# HVSUP_channel.net
KiCad netlist of a schematic drawn in Altium Designer
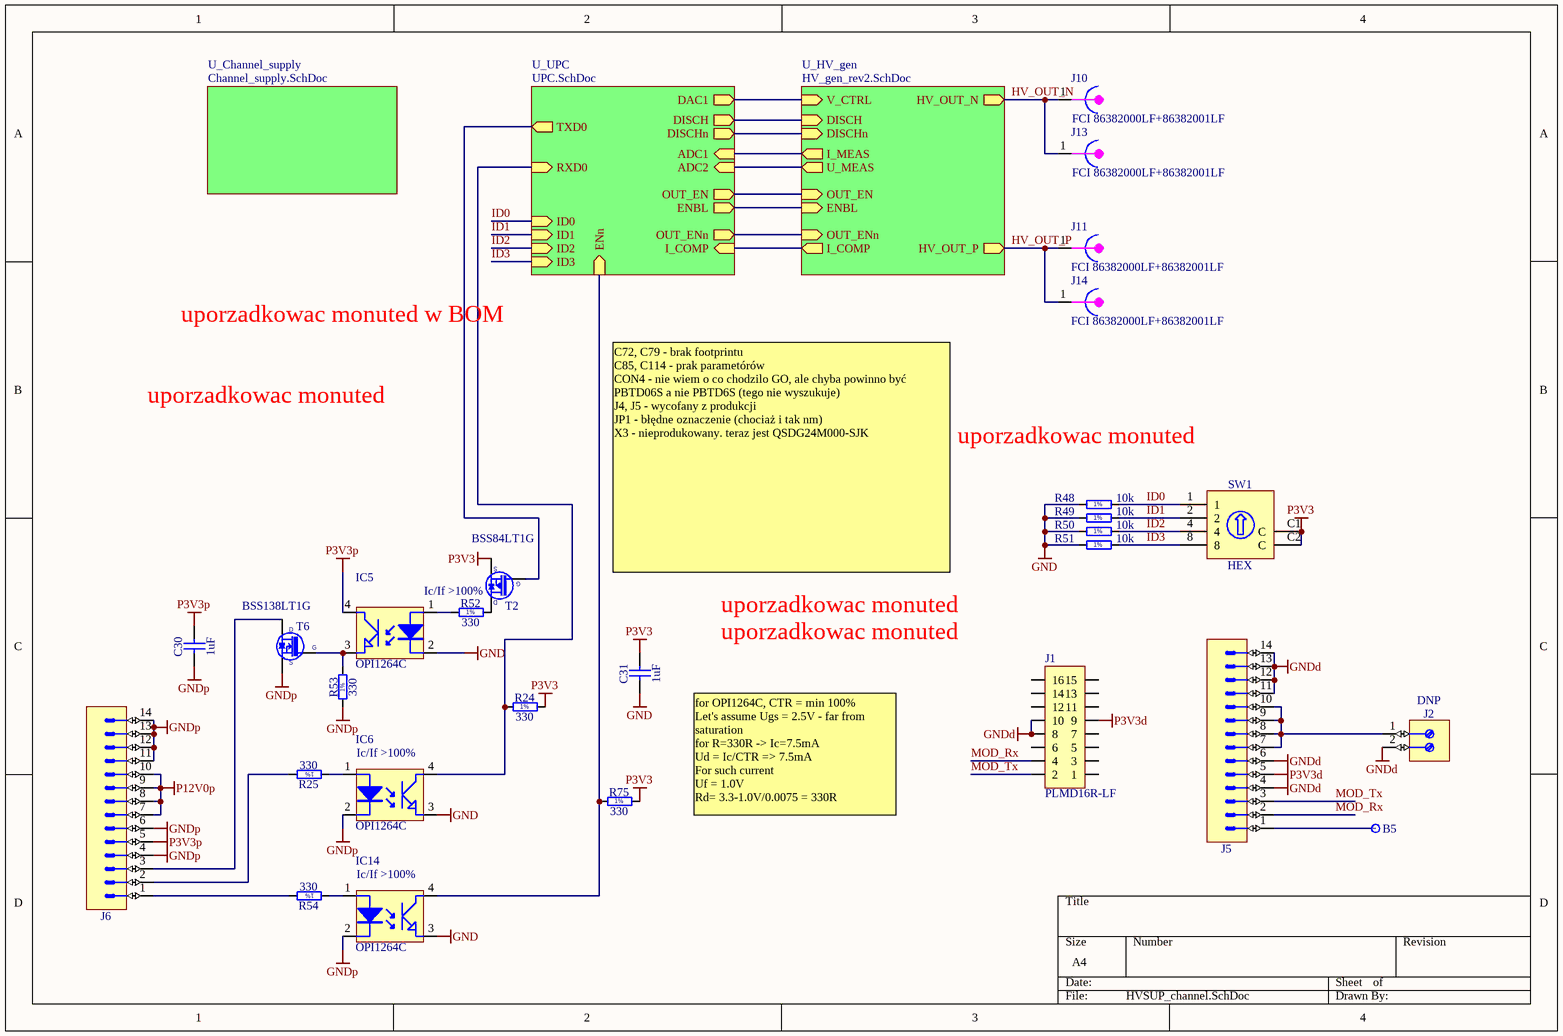
[diagram p0: HVSUP_channel.SchDoc]

(export (version "E")
  (design (tool "Eeschema 10.0.6"))
  (components
    (comp (ref "B5")
      (value "Plated Hole")
      (footprint "c130h80")
      (description "Single Terminal Socket")
      (fields (field (name "PART NUMBER") "PLATED_HOLE0.8_PAD1.3") (field (name "AUTHOR") "CERN DEM JLC"))
      (libsource (lib "Eletro-mechanical") (part "Single Terminal Socket"))
    )
    (comp (ref "C30")
      (value "1uF")
      (footprint "CAPC1005X55N")
      (description "Non-polarised capacitor")
      (fields
        (field (name "PART NUMBER") "CC0402_1UF_16V_10%_X5R")
        (field (name "VOLTAGE") "16V")
        (field (name "AUTHOR") "CERN DEM JLC")
      )
      (libsource (lib "Capacitors") (part "Capacitor - non polarized"))
    )
    (comp (ref "C31")
      (value "1uF")
      (footprint "CAPC1005X55N")
      (description "Non-polarised capacitor")
      (fields
        (field (name "PART NUMBER") "CC0402_1UF_16V_10%_X5R")
        (field (name "VOLTAGE") "16V")
        (field (name "AUTHOR") "CERN DEM JLC")
      )
      (libsource (lib "Capacitors") (part "Capacitor - non polarized"))
    )
    (comp (ref "IC5")
      (value "OPI1264C")
      (footprint "OPI1264C")
      (description "10kV opto-coupler")
      (libsource (lib "LIBRARY_SCH") (part "OPTO-OPI1264C"))
    )
    (comp (ref "IC6")
      (value "OPI1264C")
      (footprint "OPI1264C")
      (description "10kV opto-coupler")
      (libsource (lib "") (part "OPTO-OPI1264C_1"))
    )
    (comp (ref "IC14")
      (value "OPI1264C")
      (footprint "OPI1264C")
      (description "10kV opto-coupler")
      (libsource (lib "") (part "OPTO-OPI1264C_1"))
    )
    (comp (ref "J1")
      (value "PLMD16R-LF")
      (footprint "PLMD16R-LF")
      (description "2mm  dual row goldpin (Maritex)")
      (libsource (lib "LIBRARY_SCH") (part "CON_2x8 2mm_RA_male"))
    )
    (comp (ref "J2")
      (value "DNP")
      (footprint "PHOENIX_1725656")
      (description "Terminal Block, 2 Positions, Screw Connection")
      (fields
        (field (name "PART NUMBER") "PHOENIX_1725656")
        (field (name "MANUFACTURER") "PHOENIX CONTACT")
        (field (name "AUTHOR") "CERN DEM JMW")
      )
      (libsource (lib "Connectors") (part "Terminal Block_2 Positions_Screw Connection"))
    )
    (comp (ref "J5")
      (value "Header 14")
      (footprint "3M_N2514-5002RB")
      (description "Connector 14 Male")
      (fields
        (field (name "PART NUMBER") "3M_N2514-5002RB")
        (field (name "MANUFACTURER") "3M")
        (field (name "AUTHOR") "CERN DEM JLC")
      )
      (libsource (lib "Connectors") (part "Connector 14 Male"))
    )
    (comp (ref "J6")
      (value "Header 14")
      (footprint "3M_N2514-5002RB")
      (description "Connector 14 Male")
      (fields
        (field (name "PART NUMBER") "3M_N2514-5002RB")
        (field (name "MANUFACTURER") "3M")
        (field (name "AUTHOR") "CERN DEM JLC")
      )
      (libsource (lib "Connectors") (part "Connector 14 Male"))
    )
    (comp (ref "J10")
      (value "FCI 86382000LF+86382001LF")
      (footprint "FCI_86382000LF")
      (description "D-SUB HIGH VOLTAGE CONTACT PIN")
      (libsource (lib "LIBRARY_SCH") (part "CON_HV_DSUB_PIN"))
    )
    (comp (ref "J11")
      (value "FCI 86382000LF+86382001LF")
      (footprint "FCI_86382000LF")
      (description "D-SUB HIGH VOLTAGE CONTACT PIN")
      (libsource (lib "LIBRARY_SCH") (part "CON_HV_DSUB_PIN"))
    )
    (comp (ref "J13")
      (value "FCI 86382000LF+86382001LF")
      (footprint "FCI_86382000LF")
      (description "D-SUB HIGH VOLTAGE CONTACT PIN")
      (libsource (lib "LIBRARY_SCH") (part "CON_HV_DSUB_PIN"))
    )
    (comp (ref "J14")
      (value "FCI 86382000LF+86382001LF")
      (footprint "FCI_86382000LF")
      (description "D-SUB HIGH VOLTAGE CONTACT PIN")
      (libsource (lib "LIBRARY_SCH") (part "CON_HV_DSUB_PIN"))
    )
    (comp (ref "R24")
      (value "330")
      (footprint "RESC1005X40N")
      (description "Resistor - 1%")
      (fields
        (field (name "PART NUMBER") "R0402_330R_1%_0.0625W_100PPM")
        (field (name "POWER") "0.0625W")
        (field (name "AUTHOR") "CERN DEM JLC")
      )
      (libsource (lib "Resistors") (part "Resistor - 1%"))
    )
    (comp (ref "R25")
      (value "330")
      (footprint "RESC1005X40N")
      (description "Resistor - 1%")
      (fields
        (field (name "PART NUMBER") "R0402_330R_1%_0.0625W_100PPM")
        (field (name "POWER") "0.0625W")
        (field (name "AUTHOR") "CERN DEM JLC")
      )
      (libsource (lib "Resistors") (part "Resistor - 1%"))
    )
    (comp (ref "R48")
      (value "10k")
      (footprint "RESC1005X40N")
      (description "Resistor - 1%")
      (fields
        (field (name "PART NUMBER") "R0402_10K_1%_0.0625W_100PPM")
        (field (name "POWER") "0.0625W")
        (field (name "AUTHOR") "CERN DEM JLC")
      )
      (libsource (lib "Resistors") (part "Resistor - 1%"))
    )
    (comp (ref "R49")
      (value "10k")
      (footprint "RESC1005X40N")
      (description "Resistor - 1%")
      (fields
        (field (name "PART NUMBER") "R0402_10K_1%_0.0625W_100PPM")
        (field (name "POWER") "0.0625W")
        (field (name "AUTHOR") "CERN DEM JLC")
      )
      (libsource (lib "Resistors") (part "Resistor - 1%"))
    )
    (comp (ref "R50")
      (value "10k")
      (footprint "RESC1005X40N")
      (description "Resistor - 1%")
      (fields
        (field (name "PART NUMBER") "R0402_10K_1%_0.0625W_100PPM")
        (field (name "POWER") "0.0625W")
        (field (name "AUTHOR") "CERN DEM JLC")
      )
      (libsource (lib "Resistors") (part "Resistor - 1%"))
    )
    (comp (ref "R51")
      (value "10k")
      (footprint "RESC1005X40N")
      (description "Resistor - 1%")
      (fields
        (field (name "PART NUMBER") "R0402_10K_1%_0.0625W_100PPM")
        (field (name "POWER") "0.0625W")
        (field (name "AUTHOR") "CERN DEM JLC")
      )
      (libsource (lib "Resistors") (part "Resistor - 1%"))
    )
    (comp (ref "R52")
      (value "330")
      (footprint "RESC1005X40N")
      (description "Resistor - 1%")
      (fields
        (field (name "PART NUMBER") "R0402_330R_1%_0.0625W_100PPM")
        (field (name "POWER") "0.0625W")
        (field (name "AUTHOR") "CERN DEM JLC")
      )
      (libsource (lib "Resistors") (part "Resistor - 1%"))
    )
    (comp (ref "R53")
      (value "330")
      (footprint "RESC1005X40N")
      (description "Resistor - 1%")
      (fields
        (field (name "PART NUMBER") "R0402_330R_1%_0.0625W_100PPM")
        (field (name "POWER") "0.0625W")
        (field (name "AUTHOR") "CERN DEM JLC")
      )
      (libsource (lib "Resistors") (part "Resistor - 1%"))
    )
    (comp (ref "R54")
      (value "330")
      (footprint "RESC1005X40N")
      (description "Resistor - 1%")
      (fields
        (field (name "PART NUMBER") "R0402_330R_1%_0.0625W_100PPM")
        (field (name "POWER") "0.0625W")
        (field (name "AUTHOR") "CERN DEM JLC")
      )
      (libsource (lib "Resistors") (part "Resistor - 1%"))
    )
    (comp (ref "R75")
      (value "330")
      (footprint "RESC1005X40N")
      (description "Resistor - 1%")
      (fields
        (field (name "PART NUMBER") "R0402_330R_1%_0.0625W_100PPM")
        (field (name "POWER") "0.0625W")
        (field (name "AUTHOR") "CERN DEM JLC")
      )
      (libsource (lib "Resistors") (part "Resistor - 1%"))
    )
    (comp (ref "SW1")
      (value "HEX")
      (footprint "SW_OMRON_A6RV-162RF")
      (description "Rotary Code Switch 1 2 4 8 C1 C2")
      (fields
        (field (name "PART NUMBER") "SW_OMRON_A6RV-162RF or ERD716RR")
        (field (name "MANUFACTURER") "OMRON")
        (field (name "AUTHOR") "CERN DEM JLC")
      )
      (libsource (lib "Eletro-mechanical") (part "SW Rotary 1 2 4 8 C1 C2"))
    )
    (comp (ref "T2")
      (value "BSS84LT1G")
      (footprint "SOT95P240X110-3N")
      (description "P-CHANNEL MOSFET WITH DIODE")
      (fields (field (name "MANUFACTURER") "ON SEMICONDUCTOR") (field (name "AUTHOR") "CERN DEM JLC"))
      (libsource (lib "ICs And Semiconductors") (part "P-MOSFET-D 1G 2S 3D"))
    )
    (comp (ref "T6")
      (value "BSS138LT1G")
      (footprint "SOT95P240X110-3N")
      (description "N-CHANNEL MOSFET WITH DIODE")
      (fields (field (name "MANUFACTURER") "ON SEMICONDUCTOR") (field (name "AUTHOR") "CERN DEM JLC"))
      (libsource (lib "ICs And Semiconductors") (part "N-MOSFET-D 1G 2S 3D"))
    )
  )
  (nets
    (net (code "5") (name "/ENn") (class "Default")
      (node (ref "IC14") (pin "4") (pinfunction "C_4") (pintype "passive"))
      (node (ref "R75") (pin "1") (pinfunction "1_1") (pintype "passive"))
    )
    (net (code "6") (name "/HV_OUT_N") (class "Default")
      (node (ref "J10") (pin "1") (pintype "passive"))
      (node (ref "J13") (pin "1") (pintype "passive"))
    )
    (net (code "7") (name "/HV_OUT_P") (class "Default")
      (node (ref "J11") (pin "1") (pintype "passive"))
      (node (ref "J14") (pin "1") (pintype "passive"))
    )
    (net (code "8") (name "/ID0") (class "Default")
      (node (ref "R48") (pin "2") (pinfunction "2_2") (pintype "passive"))
      (node (ref "SW1") (pin "1") (pinfunction "1_1") (pintype "passive"))
    )
    (net (code "9") (name "/ID1") (class "Default")
      (node (ref "R49") (pin "2") (pinfunction "2_2") (pintype "passive"))
      (node (ref "SW1") (pin "2") (pinfunction "2_2") (pintype "passive"))
    )
    (net (code "10") (name "/ID2") (class "Default")
      (node (ref "R50") (pin "2") (pinfunction "2_2") (pintype "passive"))
      (node (ref "SW1") (pin "4") (pinfunction "4_4") (pintype "passive"))
    )
    (net (code "11") (name "/ID3") (class "Default")
      (node (ref "R51") (pin "2") (pinfunction "2_2") (pintype "passive"))
      (node (ref "SW1") (pin "8") (pinfunction "8_8") (pintype "passive"))
    )
    (net (code "14") (name "/MOD_Rx") (class "Default")
      (node (ref "J1") (pin "4") (pinfunction "4_4") (pintype "passive"))
      (node (ref "J5") (pin "2") (pinfunction "2_2") (pintype "bidirectional"))
    )
    (net (code "15") (name "/MOD_Tx") (class "Default")
      (node (ref "J1") (pin "2") (pinfunction "2_2") (pintype "passive"))
      (node (ref "J5") (pin "3") (pinfunction "3_3") (pintype "bidirectional"))
    )
    (net (code "18") (name "/RXD0") (class "Default")
      (node (ref "IC6") (pin "4") (pinfunction "C_4") (pintype "passive"))
      (node (ref "R24") (pin "1") (pinfunction "1_1") (pintype "passive"))
    )
    (net (code "19") (name "/TXD0") (class "Default")
      (node (ref "T2") (pin "1") (pinfunction "G_1") (pintype "passive"))
    )
    (net (code "21") (name "GND") (class "Default")
      (node (ref "C31") (pin "1") (pinfunction "1_1") (pintype "passive"))
      (node (ref "IC14") (pin "3") (pinfunction "E_3") (pintype "passive"))
      (node (ref "IC5") (pin "2") (pinfunction "K_2") (pintype "passive"))
      (node (ref "IC6") (pin "3") (pinfunction "E_3") (pintype "passive"))
      (node (ref "R48") (pin "1") (pinfunction "1_1") (pintype "passive"))
      (node (ref "R49") (pin "1") (pinfunction "1_1") (pintype "passive"))
      (node (ref "R50") (pin "1") (pinfunction "1_1") (pintype "passive"))
      (node (ref "R51") (pin "1") (pinfunction "1_1") (pintype "passive"))
    )
    (net (code "22") (name "GNDd") (class "Default")
      (node (ref "J1") (pin "10") (pinfunction "10_10") (pintype "passive"))
      (node (ref "J1") (pin "8") (pinfunction "8_8") (pintype "passive"))
      (node (ref "J2") (pin "2") (pinfunction "2_2") (pintype "bidirectional"))
      (node (ref "J5") (pin "11") (pinfunction "11_11") (pintype "bidirectional"))
      (node (ref "J5") (pin "12") (pinfunction "12_12") (pintype "bidirectional"))
      (node (ref "J5") (pin "13") (pinfunction "13_13") (pintype "bidirectional"))
      (node (ref "J5") (pin "14") (pinfunction "14_14") (pintype "bidirectional"))
      (node (ref "J5") (pin "4") (pinfunction "4_4") (pintype "bidirectional"))
      (node (ref "J5") (pin "6") (pinfunction "6_6") (pintype "bidirectional"))
    )
    (net (code "23") (name "GNDp") (class "Default")
      (node (ref "C30") (pin "1") (pinfunction "1_1") (pintype "passive"))
      (node (ref "IC14") (pin "2") (pinfunction "K_2") (pintype "passive"))
      (node (ref "IC6") (pin "2") (pinfunction "K_2") (pintype "passive"))
      (node (ref "J6") (pin "11") (pinfunction "11_11") (pintype "bidirectional"))
      (node (ref "J6") (pin "12") (pinfunction "12_12") (pintype "bidirectional"))
      (node (ref "J6") (pin "13") (pinfunction "13_13") (pintype "bidirectional"))
      (node (ref "J6") (pin "14") (pinfunction "14_14") (pintype "bidirectional"))
      (node (ref "J6") (pin "4") (pinfunction "4_4") (pintype "bidirectional"))
      (node (ref "J6") (pin "6") (pinfunction "6_6") (pintype "bidirectional"))
      (node (ref "R53") (pin "1") (pinfunction "1_1") (pintype "passive"))
      (node (ref "T6") (pin "2") (pinfunction "S_2") (pintype "passive"))
    )
    (net (code "24") (name "Net-(B5-Pad1)") (class "Default")
      (node (ref "B5") (pin "1") (pinfunction "1_1") (pintype "bidirectional"))
      (node (ref "J5") (pin "1") (pinfunction "1_1") (pintype "bidirectional"))
    )
    (net (code "25") (name "Net-(IC5-A)") (class "Default")
      (node (ref "IC5") (pin "1") (pinfunction "A_1") (pintype "passive"))
      (node (ref "R52") (pin "1") (pinfunction "1_1") (pintype "passive"))
    )
    (net (code "26") (name "Net-(IC5-E)") (class "Default")
      (node (ref "IC5") (pin "3") (pinfunction "E_3") (pintype "passive"))
      (node (ref "R53") (pin "2") (pinfunction "2_2") (pintype "passive"))
      (node (ref "T6") (pin "1") (pinfunction "G_1") (pintype "passive"))
    )
    (net (code "27") (name "Net-(IC6-A)") (class "Default")
      (node (ref "IC6") (pin "1") (pinfunction "A_1") (pintype "passive"))
      (node (ref "R25") (pin "1") (pinfunction "1_1") (pintype "passive"))
    )
    (net (code "28") (name "Net-(IC14-A)") (class "Default")
      (node (ref "IC14") (pin "1") (pinfunction "A_1") (pintype "passive"))
      (node (ref "R54") (pin "1") (pinfunction "1_1") (pintype "passive"))
    )
    (net (code "29") (name "Net-(J2-Pad1)") (class "Default")
      (node (ref "J2") (pin "1") (pinfunction "1_1") (pintype "bidirectional"))
      (node (ref "J5") (pin "10") (pinfunction "10_10") (pintype "bidirectional"))
      (node (ref "J5") (pin "7") (pinfunction "7_7") (pintype "bidirectional"))
      (node (ref "J5") (pin "8") (pinfunction "8_8") (pintype "bidirectional"))
      (node (ref "J5") (pin "9") (pinfunction "9_9") (pintype "bidirectional"))
    )
    (net (code "30") (name "Net-(J6-Pad1)") (class "Default")
      (node (ref "J6") (pin "1") (pinfunction "1_1") (pintype "bidirectional"))
      (node (ref "R54") (pin "2") (pinfunction "2_2") (pintype "passive"))
    )
    (net (code "31") (name "Net-(J6-Pad2)") (class "Default")
      (node (ref "J6") (pin "2") (pinfunction "2_2") (pintype "bidirectional"))
      (node (ref "R25") (pin "2") (pinfunction "2_2") (pintype "passive"))
    )
    (net (code "32") (name "Net-(T2-D)") (class "Default")
      (node (ref "R52") (pin "2") (pinfunction "2_2") (pintype "passive"))
      (node (ref "T2") (pin "3") (pinfunction "D_3") (pintype "passive"))
    )
    (net (code "33") (name "Net-(T6-D)") (class "Default")
      (node (ref "J6") (pin "3") (pinfunction "3_3") (pintype "bidirectional"))
      (node (ref "T6") (pin "3") (pinfunction "D_3") (pintype "passive"))
    )
    (net (code "34") (name "P3V3") (class "Default")
      (node (ref "C31") (pin "2") (pinfunction "2_2") (pintype "passive"))
      (node (ref "R24") (pin "2") (pinfunction "2_2") (pintype "passive"))
      (node (ref "R75") (pin "2") (pinfunction "2_2") (pintype "passive"))
      (node (ref "SW1") (pin "C1") (pinfunction "C_C1") (pintype "passive"))
      (node (ref "SW1") (pin "C2") (pinfunction "C_C2") (pintype "passive"))
      (node (ref "T2") (pin "2") (pinfunction "S_2") (pintype "passive"))
    )
    (net (code "35") (name "P3V3d") (class "Default")
      (node (ref "J1") (pin "9") (pinfunction "9_9") (pintype "passive"))
      (node (ref "J5") (pin "5") (pinfunction "5_5") (pintype "bidirectional"))
    )
    (net (code "36") (name "P3V3p") (class "Default")
      (node (ref "C30") (pin "2") (pinfunction "2_2") (pintype "passive"))
      (node (ref "IC5") (pin "4") (pinfunction "C_4") (pintype "passive"))
      (node (ref "J6") (pin "5") (pinfunction "5_5") (pintype "bidirectional"))
    )
    (net (code "37") (name "P12V0p") (class "Default")
      (node (ref "J6") (pin "10") (pinfunction "10_10") (pintype "bidirectional"))
      (node (ref "J6") (pin "7") (pinfunction "7_7") (pintype "bidirectional"))
      (node (ref "J6") (pin "8") (pinfunction "8_8") (pintype "bidirectional"))
      (node (ref "J6") (pin "9") (pinfunction "9_9") (pintype "bidirectional"))
    )
    (net (code "38") (name "unconnected-(J1-Pad1)") (class "Default")
      (node (ref "J1") (pin "1") (pinfunction "1_1") (pintype "passive"))
    )
    (net (code "39") (name "unconnected-(J1-Pad3)") (class "Default")
      (node (ref "J1") (pin "3") (pinfunction "3_3") (pintype "passive"))
    )
    (net (code "40") (name "unconnected-(J1-Pad5)") (class "Default")
      (node (ref "J1") (pin "5") (pinfunction "5_5") (pintype "passive"))
    )
    (net (code "41") (name "unconnected-(J1-Pad6)") (class "Default")
      (node (ref "J1") (pin "6") (pinfunction "6_6") (pintype "passive"))
    )
    (net (code "42") (name "unconnected-(J1-Pad7)") (class "Default")
      (node (ref "J1") (pin "7") (pinfunction "7_7") (pintype "passive"))
    )
    (net (code "43") (name "unconnected-(J1-Pad11)") (class "Default")
      (node (ref "J1") (pin "11") (pinfunction "11_11") (pintype "passive"))
    )
    (net (code "44") (name "unconnected-(J1-Pad12)") (class "Default")
      (node (ref "J1") (pin "12") (pinfunction "12_12") (pintype "passive"))
    )
    (net (code "45") (name "unconnected-(J1-Pad13)") (class "Default")
      (node (ref "J1") (pin "13") (pinfunction "13_13") (pintype "passive"))
    )
    (net (code "46") (name "unconnected-(J1-Pad14)") (class "Default")
      (node (ref "J1") (pin "14") (pinfunction "14_14") (pintype "passive"))
    )
    (net (code "47") (name "unconnected-(J1-Pad15)") (class "Default")
      (node (ref "J1") (pin "15") (pinfunction "15_15") (pintype "passive"))
    )
    (net (code "48") (name "unconnected-(J1-Pad16)") (class "Default")
      (node (ref "J1") (pin "16") (pinfunction "16_16") (pintype "passive"))
    )
  )
)
